# Power_Supply.net
KiCad netlist of a schematic drawn in Altium Designer
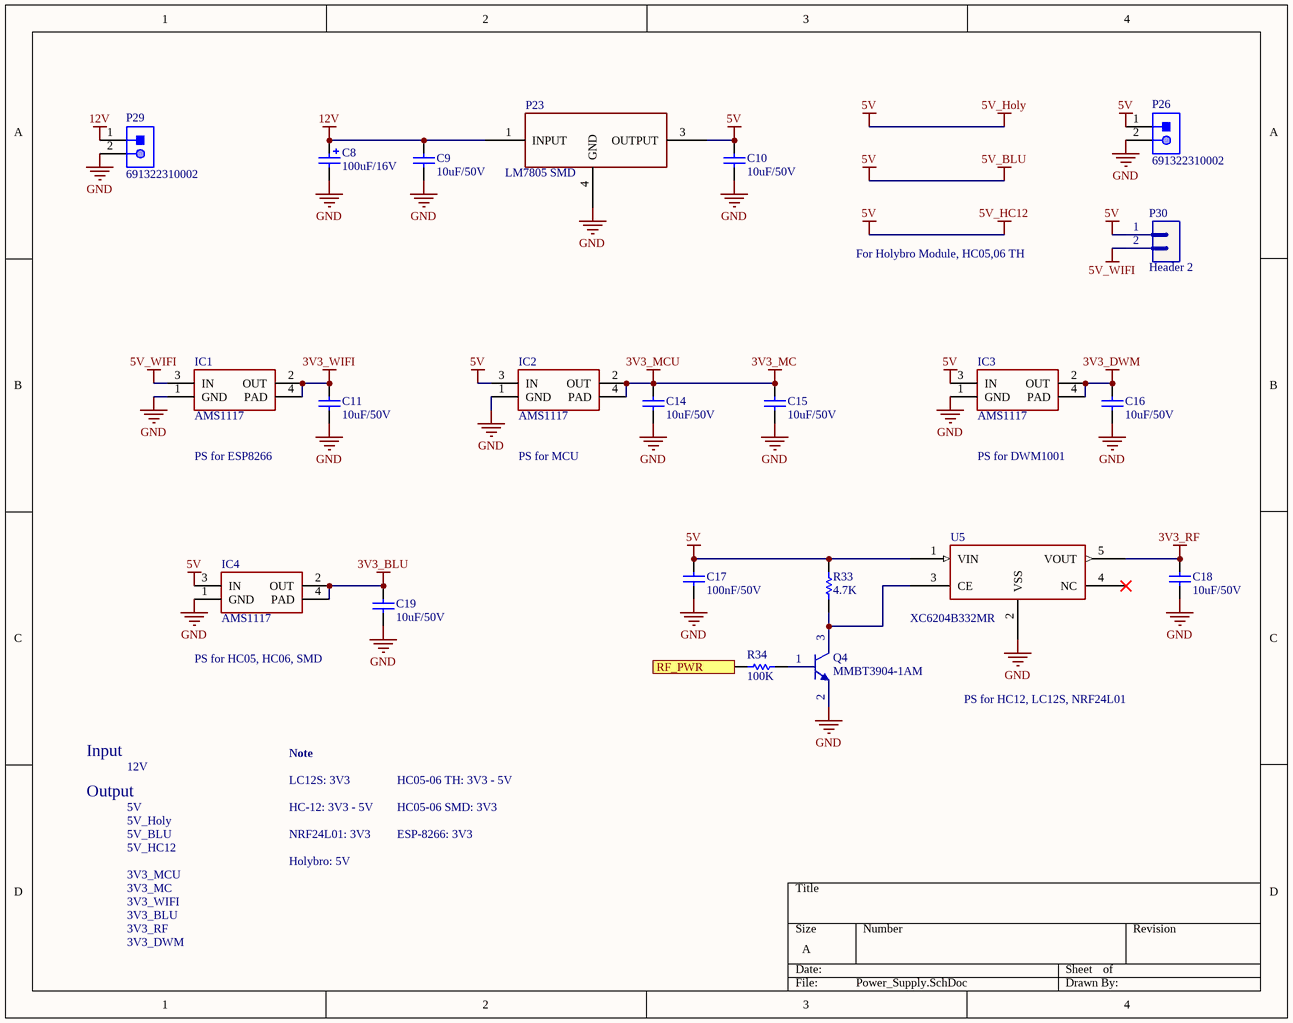
[diagram p0: Power_Supply.SchDoc]

(export (version "E")
  (design (tool "Eeschema 10.0.6"))
  (components
    (comp (ref "C8")
      (value "100uF/16V")
      (footprint "Capacitor:CAP-SM-AL-SIZE-D-D6L6")
      (description "CAP ALUM 100UF 20% 16V SMD")
      (fields
        (field (name "MANUFACTURER") "Nichicon")
        (field (name "MANUFACTURER PART NUMBER") "UWX1C101MCL1GB")
      )
      (libsource (lib "Capacitor") (part "Cap-Al-100uF-16V-D6L5"))
    )
    (comp (ref "C9")
      (value "10uF/50V")
      (footprint "CAP-SM-0805")
      (description "CAP CER 10UF 50V X5R 0805")
      (fields
        (field (name "MANUFACTURER") "Yageo")
        (field (name "MANUFACTURER PART NUMBER") "CC0805KKX5R9BB106")
      )
      (libsource (lib "Capacitor") (part "Cap-10uF-50V-0805"))
    )
    (comp (ref "C10")
      (value "10uF/50V")
      (footprint "CAP-SM-0805")
      (description "CAP CER 10UF 50V X5R 0805")
      (fields
        (field (name "MANUFACTURER") "Yageo")
        (field (name "MANUFACTURER PART NUMBER") "CC0805KKX5R9BB106")
      )
      (libsource (lib "Capacitor") (part "Cap-10uF-50V-0805"))
    )
    (comp (ref "C11")
      (value "10uF/50V")
      (footprint "CAP-SM-0805")
      (description "CAP CER 10UF 50V X5R 0805")
      (fields
        (field (name "MANUFACTURER") "Yageo")
        (field (name "MANUFACTURER PART NUMBER") "CC0805KKX5R9BB106")
      )
      (libsource (lib "Capacitor") (part "Cap-10uF-50V-0805"))
    )
    (comp (ref "C14")
      (value "10uF/50V")
      (footprint "CAP-SM-0805")
      (description "CAP CER 10UF 50V X5R 0805")
      (fields
        (field (name "MANUFACTURER") "Yageo")
        (field (name "MANUFACTURER PART NUMBER") "CC0805KKX5R9BB106")
      )
      (libsource (lib "Capacitor") (part "Cap-10uF-50V-0805"))
    )
    (comp (ref "C15")
      (value "10uF/50V")
      (footprint "CAP-SM-0805")
      (description "CAP CER 10UF 50V X5R 0805")
      (fields
        (field (name "MANUFACTURER") "Yageo")
        (field (name "MANUFACTURER PART NUMBER") "CC0805KKX5R9BB106")
      )
      (libsource (lib "Capacitor") (part "Cap-10uF-50V-0805"))
    )
    (comp (ref "C16")
      (value "10uF/50V")
      (footprint "CAP-SM-0805")
      (description "CAP CER 10UF 50V X5R 0805")
      (fields
        (field (name "MANUFACTURER") "Yageo")
        (field (name "MANUFACTURER PART NUMBER") "CC0805KKX5R9BB106")
      )
      (libsource (lib "Capacitor") (part "Cap-10uF-50V-0805"))
    )
    (comp (ref "C17")
      (value "100nF/50V")
      (footprint "CAP-SM-0805")
      (description "CAP CER 0.1UF 50V Y5V 0805")
      (fields
        (field (name "MANUFACTURER") "Samsung Electro-Mechanics")
        (field (name "MANUFACTURER PART NUMBER") "CL21F104ZBCNNNC")
      )
      (libsource (lib "Capacitor") (part "Cap-100nF-50V-0805"))
    )
    (comp (ref "C18")
      (value "10uF/50V")
      (footprint "CAP-SM-0805")
      (description "CAP CER 10UF 50V X5R 0805")
      (fields
        (field (name "MANUFACTURER") "Yageo")
        (field (name "MANUFACTURER PART NUMBER") "CC0805KKX5R9BB106")
      )
      (libsource (lib "Capacitor") (part "Cap-10uF-50V-0805"))
    )
    (comp (ref "C19")
      (value "10uF/50V")
      (footprint "CAP-SM-0805")
      (description "CAP CER 10UF 50V X5R 0805")
      (fields
        (field (name "MANUFACTURER") "Yageo")
        (field (name "MANUFACTURER PART NUMBER") "CC0805KKX5R9BB106")
      )
      (libsource (lib "Capacitor") (part "Cap-10uF-50V-0805"))
    )
    (comp (ref "IC1")
      (value "AMS1117")
      (footprint "PI:SOT223")
      (description "Available in 1.8V, 2.5V, 2.85V, 3.3V, 5V, and  Adjustable Versions")
      (libsource (lib "PI") (part "AMS1117"))
    )
    (comp (ref "IC2")
      (value "AMS1117")
      (footprint "PI:SOT223")
      (description "Available in 1.8V, 2.5V, 2.85V, 3.3V, 5V, and  Adjustable Versions")
      (libsource (lib "PI") (part "AMS1117"))
    )
    (comp (ref "IC3")
      (value "AMS1117")
      (footprint "PI:SOT223")
      (description "Available in 1.8V, 2.5V, 2.85V, 3.3V, 5V, and  Adjustable Versions")
      (libsource (lib "PI") (part "AMS1117"))
    )
    (comp (ref "IC4")
      (value "AMS1117")
      (footprint "PI:SOT223")
      (description "Available in 1.8V, 2.5V, 2.85V, 3.3V, 5V, and  Adjustable Versions")
      (libsource (lib "PI") (part "AMS1117"))
    )
    (comp (ref "P23")
      (value "LM7805 SMD")
      (footprint "D2PAK_STM")
      (libsource (lib "PIF_robot") (part "LM7805 SMD"))
    )
    (comp (ref "P26")
      (value "691322310002")
      (footprint "691322310002")
      (description "WR-TBL Serie 322 Horizontal PCB Header, Pluggable, pitch 3.81mm, 2p")
      (fields (field (name "PUBLISHER") "Wurth Elektronik"))
      (libsource (lib "691322310002_Altium_WR-TBL_rev19a") (part "691322310002"))
    )
    (comp (ref "P29")
      (value "691322310002")
      (footprint "691322310002")
      (description "WR-TBL Serie 322 Horizontal PCB Header, Pluggable, pitch 3.81mm, 2p")
      (fields (field (name "PUBLISHER") "Wurth Elektronik"))
      (libsource (lib "691322310002_Altium_WR-TBL_rev19a") (part "691322310002"))
    )
    (comp (ref "P30")
      (value "Header 2")
      (footprint "JP2")
      (description "Header, 2-Pin")
      (fields (field (name "PUBLISHER") "Altium Limited"))
      (libsource (lib "PIF_C16_lib") (part "Header 2"))
    )
    (comp (ref "Q4")
      (value "MMBT3904-1AM")
      (footprint "BJT:SOT23_NEX")
      (libsource (lib "BJT") (part "MMBT3904-1AM"))
    )
    (comp (ref "R33")
      (value "4.7K")
      (footprint "Resistor:RES-SM-0805")
      (description "RES SMD 4.7K OHM 5% 1/8W 0805")
      (fields
        (field (name "MANUFACTURER") "Yageo")
        (field (name "MANUFACTURER PART NUMBER") "RC0805JR-074K7L")
      )
      (libsource (lib "Resistor") (part "Res-4.7K-0805"))
    )
    (comp (ref "R34")
      (value "100K")
      (footprint "Resistor:RES-SM-0805")
      (description "RES 0 OHM JUMPER 0805")
      (fields
        (field (name "MANUFACTURER") "Vishay Dale")
        (field (name "MANUFACTURER PART NUMBER") "WSL080500000ZEA9")
      )
      (libsource (lib "Resistor") (part "Res-100K-0805"))
    )
    (comp (ref "U5")
      (value "XC6204B332MR")
      (footprint "PI:XC6204/05_SOT-00")
      (fields (field (name "COPYRIGHT") "Copyright (C) 2018 Accelerated Designs. All rights reserved"))
      (libsource (lib "PI") (part "XC6204B332MR"))
    )
  )
  (nets
    (net (code "1") (name "/RF_PWR") (class "Default")
      (node (ref "R34") (pin "1") (pinfunction "1_1") (pintype "passive"))
    )
    (net (code "2") (name "3V3_BLU") (class "Default")
      (node (ref "C19") (pin "2") (pinfunction "2_2") (pintype "passive"))
      (node (ref "IC4") (pin "2") (pinfunction "OUT_2") (pintype "passive"))
      (node (ref "IC4") (pin "4") (pinfunction "PAD_4") (pintype "passive"))
    )
    (net (code "3") (name "3V3_DWM") (class "Default")
      (node (ref "C16") (pin "2") (pinfunction "2_2") (pintype "passive"))
      (node (ref "IC3") (pin "2") (pinfunction "OUT_2") (pintype "passive"))
      (node (ref "IC3") (pin "4") (pinfunction "PAD_4") (pintype "passive"))
    )
    (net (code "4") (name "3V3_MC") (class "Default")
      (node (ref "C14") (pin "2") (pinfunction "2_2") (pintype "passive"))
      (node (ref "C15") (pin "2") (pinfunction "2_2") (pintype "passive"))
      (node (ref "IC2") (pin "2") (pinfunction "OUT_2") (pintype "passive"))
      (node (ref "IC2") (pin "4") (pinfunction "PAD_4") (pintype "passive"))
    )
    (net (code "5") (name "3V3_RF") (class "Default")
      (node (ref "C18") (pin "2") (pinfunction "2_2") (pintype "passive"))
      (node (ref "U5") (pin "5") (pinfunction "VOUT_5") (pintype "output"))
    )
    (net (code "6") (name "3V3_WIFI") (class "Default")
      (node (ref "C11") (pin "2") (pinfunction "2_2") (pintype "passive"))
      (node (ref "IC1") (pin "2") (pinfunction "OUT_2") (pintype "passive"))
      (node (ref "IC1") (pin "4") (pinfunction "PAD_4") (pintype "passive"))
    )
    (net (code "7") (name "5V") (class "Default")
      (node (ref "C10") (pin "2") (pinfunction "2_2") (pintype "passive"))
      (node (ref "C17") (pin "2") (pinfunction "2_2") (pintype "passive"))
      (node (ref "IC2") (pin "3") (pinfunction "IN_3") (pintype "passive"))
      (node (ref "IC3") (pin "3") (pinfunction "IN_3") (pintype "passive"))
      (node (ref "IC4") (pin "3") (pinfunction "IN_3") (pintype "passive"))
      (node (ref "P23") (pin "3") (pinfunction "OUTPUT_3") (pintype "passive"))
      (node (ref "P26") (pin "1") (pinfunction "1_1") (pintype "passive"))
      (node (ref "P30") (pin "1") (pinfunction "1_1") (pintype "passive"))
      (node (ref "R33") (pin "2") (pinfunction "2_2") (pintype "passive"))
      (node (ref "U5") (pin "1") (pinfunction "VIN_1") (pintype "input"))
    )
    (net (code "8") (name "5V_WIFI") (class "Default")
      (node (ref "IC1") (pin "3") (pinfunction "IN_3") (pintype "passive"))
      (node (ref "P30") (pin "2") (pinfunction "2_2") (pintype "passive"))
    )
    (net (code "9") (name "12V") (class "Default")
      (node (ref "C8") (pin "1") (pinfunction "1_1") (pintype "passive"))
      (node (ref "C9") (pin "1") (pinfunction "1_1") (pintype "passive"))
      (node (ref "P23") (pin "1") (pinfunction "INPUT_1") (pintype "passive"))
      (node (ref "P29") (pin "1") (pinfunction "1_1") (pintype "passive"))
    )
    (net (code "10") (name "GND") (class "Default")
      (node (ref "C10") (pin "1") (pinfunction "1_1") (pintype "passive"))
      (node (ref "C11") (pin "1") (pinfunction "1_1") (pintype "passive"))
      (node (ref "C14") (pin "1") (pinfunction "1_1") (pintype "passive"))
      (node (ref "C15") (pin "1") (pinfunction "1_1") (pintype "passive"))
      (node (ref "C16") (pin "1") (pinfunction "1_1") (pintype "passive"))
      (node (ref "C17") (pin "1") (pinfunction "1_1") (pintype "passive"))
      (node (ref "C18") (pin "1") (pinfunction "1_1") (pintype "passive"))
      (node (ref "C19") (pin "1") (pinfunction "1_1") (pintype "passive"))
      (node (ref "C8") (pin "2") (pinfunction "2_2") (pintype "passive"))
      (node (ref "C9") (pin "2") (pinfunction "2_2") (pintype "passive"))
      (node (ref "IC1") (pin "1") (pinfunction "GND_1") (pintype "passive"))
      (node (ref "IC2") (pin "1") (pinfunction "GND_1") (pintype "passive"))
      (node (ref "IC3") (pin "1") (pinfunction "GND_1") (pintype "passive"))
      (node (ref "IC4") (pin "1") (pinfunction "GND_1") (pintype "passive"))
      (node (ref "P23") (pin "4") (pinfunction "GND_4") (pintype "passive"))
      (node (ref "P26") (pin "2") (pinfunction "2_2") (pintype "passive"))
      (node (ref "P29") (pin "2") (pinfunction "2_2") (pintype "passive"))
      (node (ref "Q4") (pin "2") (pinfunction "E_2") (pintype "passive"))
      (node (ref "U5") (pin "2") (pinfunction "VSS_2") (pintype "passive"))
    )
    (net (code "11") (name "Net-(Q4-B)") (class "Default")
      (node (ref "Q4") (pin "1") (pinfunction "B_1") (pintype "passive"))
      (node (ref "R34") (pin "2") (pinfunction "2_2") (pintype "passive"))
    )
    (net (code "12") (name "Net-(Q4-C)") (class "Default")
      (node (ref "Q4") (pin "3") (pinfunction "C_3") (pintype "passive"))
      (node (ref "R33") (pin "1") (pinfunction "1_1") (pintype "passive"))
      (node (ref "U5") (pin "3") (pinfunction "CE_3") (pintype "passive"))
    )
    (net (code "13") (name "unconnected-(U5-NC-Pad4)") (class "Default")
      (node (ref "U5") (pin "4") (pinfunction "NC_4") (pintype "passive+no_connect"))
    )
  )
)
